# adapter_RX2189.net
KiCad netlist of a schematic drawn in EAGLE
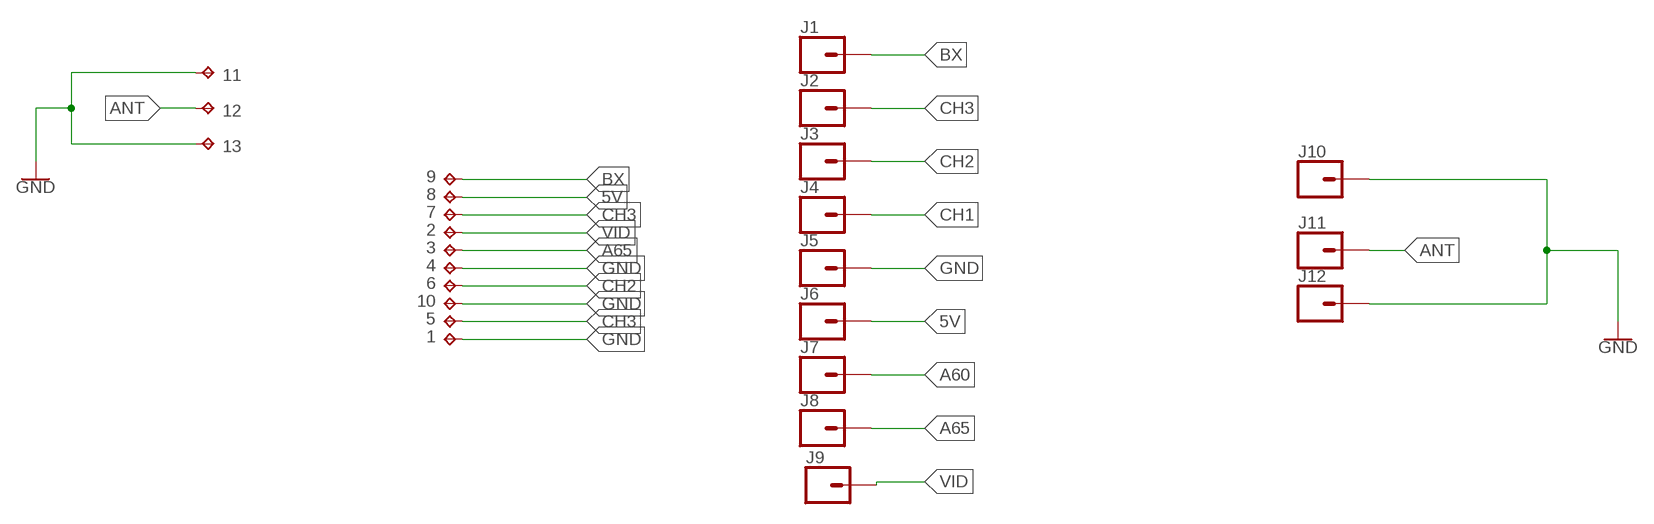
[diagram p0: schematic, sheet 1]

(export (version "E")
  (design (tool "Eeschema 10.0.6"))
  (components
    (comp (ref "1")
      (value "TPTP10SQ")
      (footprint "eagle-import:TP10SQ")
      (libsource (lib "eagle-import") (part "TPTP10SQ"))
    )
    (comp (ref "2")
      (value "TPTP10SQ")
      (footprint "eagle-import:TP10SQ")
      (libsource (lib "eagle-import") (part "TPTP10SQ"))
    )
    (comp (ref "3")
      (value "TPTP10SQ")
      (footprint "eagle-import:TP10SQ")
      (libsource (lib "eagle-import") (part "TPTP10SQ"))
    )
    (comp (ref "4")
      (value "TPTP10SQ")
      (footprint "eagle-import:TP10SQ")
      (libsource (lib "eagle-import") (part "TPTP10SQ"))
    )
    (comp (ref "5")
      (value "TPTP10SQ")
      (footprint "eagle-import:TP10SQ")
      (libsource (lib "eagle-import") (part "TPTP10SQ"))
    )
    (comp (ref "6")
      (value "TPTP10SQ")
      (footprint "eagle-import:TP10SQ")
      (libsource (lib "eagle-import") (part "TPTP10SQ"))
    )
    (comp (ref "7")
      (value "TPTP10SQ")
      (footprint "eagle-import:TP10SQ")
      (libsource (lib "eagle-import") (part "TPTP10SQ"))
    )
    (comp (ref "8")
      (value "TPTP10SQ")
      (footprint "eagle-import:TP10SQ")
      (libsource (lib "eagle-import") (part "TPTP10SQ"))
    )
    (comp (ref "9")
      (value "TPTP10SQ")
      (footprint "eagle-import:TP10SQ")
      (libsource (lib "eagle-import") (part "TPTP10SQ"))
    )
    (comp (ref "10")
      (value "TPTP10SQ")
      (footprint "eagle-import:TP10SQ")
      (libsource (lib "eagle-import") (part "TPTP10SQ"))
    )
    (comp (ref "11")
      (value "TPTP10SQ")
      (footprint "eagle-import:TP10SQ")
      (libsource (lib "eagle-import") (part "TPTP10SQ"))
    )
    (comp (ref "12")
      (value "TPTP10SQ")
      (footprint "eagle-import:TP10SQ")
      (libsource (lib "eagle-import") (part "TPTP10SQ"))
    )
    (comp (ref "13")
      (value "TPTP10SQ")
      (footprint "eagle-import:TP10SQ")
      (libsource (lib "eagle-import") (part "TPTP10SQ"))
    )
    (comp (ref "J1")
      (value "CONN_01PTH_NO_SILK_KIT")
      (footprint "eagle-import:1X01NS_KIT")
      (libsource (lib "eagle-import") (part "CONN_01PTH_NO_SILK_KIT"))
    )
    (comp (ref "J2")
      (value "CONN_01PTH_NO_SILK_KIT")
      (footprint "eagle-import:1X01NS_KIT")
      (libsource (lib "eagle-import") (part "CONN_01PTH_NO_SILK_KIT"))
    )
    (comp (ref "J3")
      (value "CONN_01PTH_NO_SILK_KIT")
      (footprint "eagle-import:1X01NS_KIT")
      (libsource (lib "eagle-import") (part "CONN_01PTH_NO_SILK_KIT"))
    )
    (comp (ref "J4")
      (value "CONN_01PTH_NO_SILK_KIT")
      (footprint "eagle-import:1X01NS_KIT")
      (libsource (lib "eagle-import") (part "CONN_01PTH_NO_SILK_KIT"))
    )
    (comp (ref "J5")
      (value "CONN_01PTH_NO_SILK_KIT")
      (footprint "eagle-import:1X01NS_KIT")
      (libsource (lib "eagle-import") (part "CONN_01PTH_NO_SILK_KIT"))
    )
    (comp (ref "J6")
      (value "CONN_01PTH_NO_SILK_KIT")
      (footprint "eagle-import:1X01NS_KIT")
      (libsource (lib "eagle-import") (part "CONN_01PTH_NO_SILK_KIT"))
    )
    (comp (ref "J7")
      (value "CONN_01PTH_NO_SILK_KIT")
      (footprint "eagle-import:1X01NS_KIT")
      (libsource (lib "eagle-import") (part "CONN_01PTH_NO_SILK_KIT"))
    )
    (comp (ref "J8")
      (value "CONN_01PTH_NO_SILK_KIT")
      (footprint "eagle-import:1X01NS_KIT")
      (libsource (lib "eagle-import") (part "CONN_01PTH_NO_SILK_KIT"))
    )
    (comp (ref "J9")
      (value "CONN_01PTH_NO_SILK_KIT")
      (footprint "eagle-import:1X01NS_KIT")
      (libsource (lib "eagle-import") (part "CONN_01PTH_NO_SILK_KIT"))
    )
    (comp (ref "J10")
      (value "CONN_01PTH_NO_SILK_KIT")
      (footprint "eagle-import:1X01NS_KIT")
      (libsource (lib "eagle-import") (part "CONN_01PTH_NO_SILK_KIT"))
    )
    (comp (ref "J11")
      (value "CONN_01PTH_NO_SILK_KIT")
      (footprint "eagle-import:1X01NS_KIT")
      (libsource (lib "eagle-import") (part "CONN_01PTH_NO_SILK_KIT"))
    )
    (comp (ref "J12")
      (value "CONN_01PTH_NO_SILK_KIT")
      (footprint "eagle-import:1X01NS_KIT")
      (libsource (lib "eagle-import") (part "CONN_01PTH_NO_SILK_KIT"))
    )
  )
  (nets
    (net (code "1") (name "5V") (class "Default")
      (node (ref "8") (pin "TP") (pinfunction "TP_TP") (pintype "input"))
      (node (ref "J6") (pin "1") (pinfunction "1_1") (pintype "passive"))
    )
    (net (code "2") (name "A60") (class "Default")
      (node (ref "J7") (pin "1") (pinfunction "1_1") (pintype "passive"))
    )
    (net (code "3") (name "A65") (class "Default")
      (node (ref "3") (pin "TP") (pinfunction "TP_TP") (pintype "input"))
      (node (ref "J8") (pin "1") (pinfunction "1_1") (pintype "passive"))
    )
    (net (code "4") (name "ANT") (class "Default")
      (node (ref "12") (pin "TP") (pinfunction "TP_TP") (pintype "input"))
      (node (ref "J11") (pin "1") (pinfunction "1_1") (pintype "passive"))
    )
    (net (code "5") (name "BX") (class "Default")
      (node (ref "9") (pin "TP") (pinfunction "TP_TP") (pintype "input"))
      (node (ref "J1") (pin "1") (pinfunction "1_1") (pintype "passive"))
    )
    (net (code "6") (name "CH1") (class "Default")
      (node (ref "J4") (pin "1") (pinfunction "1_1") (pintype "passive"))
    )
    (net (code "7") (name "CH2") (class "Default")
      (node (ref "6") (pin "TP") (pinfunction "TP_TP") (pintype "input"))
      (node (ref "J3") (pin "1") (pinfunction "1_1") (pintype "passive"))
    )
    (net (code "8") (name "CH3") (class "Default")
      (node (ref "5") (pin "TP") (pinfunction "TP_TP") (pintype "input"))
      (node (ref "7") (pin "TP") (pinfunction "TP_TP") (pintype "input"))
      (node (ref "J2") (pin "1") (pinfunction "1_1") (pintype "passive"))
    )
    (net (code "9") (name "GND") (class "Default")
      (node (ref "1") (pin "TP") (pinfunction "TP_TP") (pintype "input"))
      (node (ref "10") (pin "TP") (pinfunction "TP_TP") (pintype "input"))
      (node (ref "11") (pin "TP") (pinfunction "TP_TP") (pintype "input"))
      (node (ref "13") (pin "TP") (pinfunction "TP_TP") (pintype "input"))
      (node (ref "4") (pin "TP") (pinfunction "TP_TP") (pintype "input"))
      (node (ref "J10") (pin "1") (pinfunction "1_1") (pintype "passive"))
      (node (ref "J12") (pin "1") (pinfunction "1_1") (pintype "passive"))
      (node (ref "J5") (pin "1") (pinfunction "1_1") (pintype "passive"))
    )
    (net (code "10") (name "VID") (class "Default")
      (node (ref "2") (pin "TP") (pinfunction "TP_TP") (pintype "input"))
      (node (ref "J9") (pin "1") (pinfunction "1_1") (pintype "passive"))
    )
  )
)
